# 4_cpu.net
KiCad netlist of a schematic drawn in Altium Designer
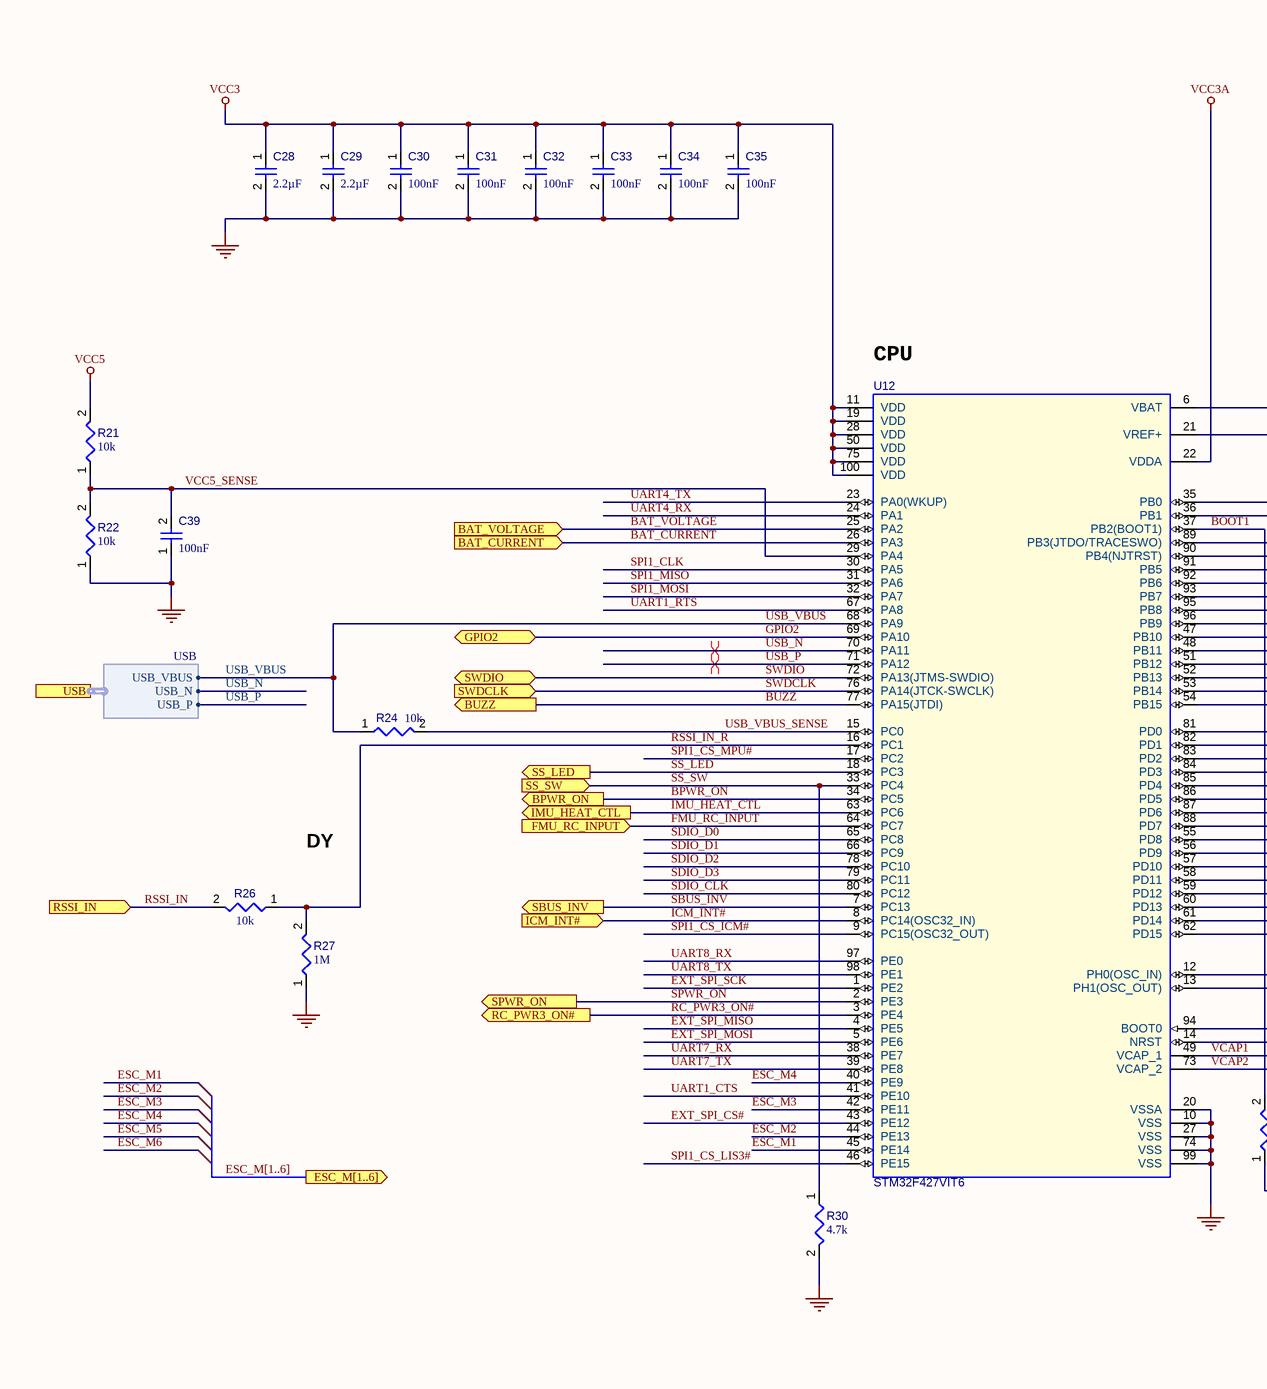
[diagram p0:  4_cpu.SchDoc, left]
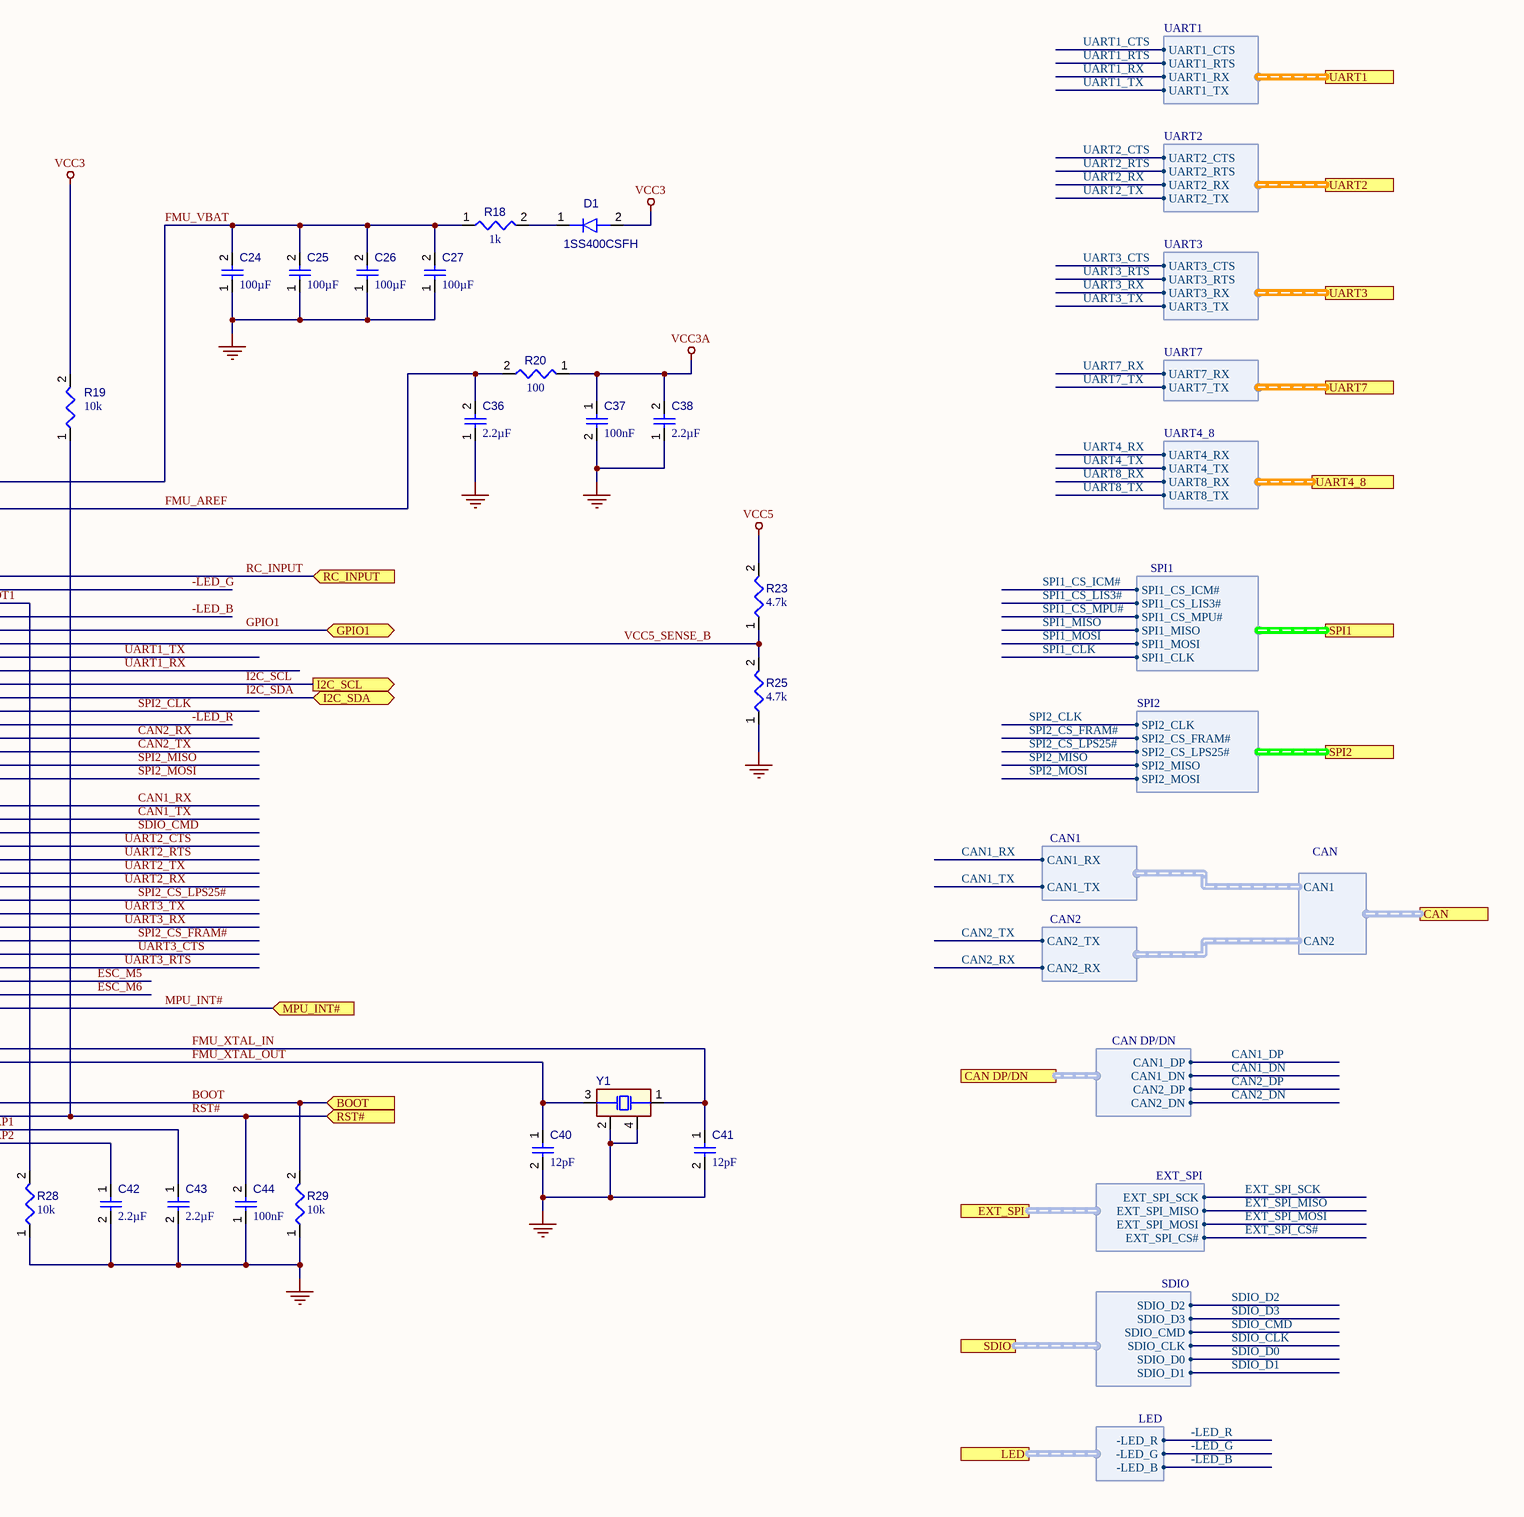
[diagram p1:  4_cpu.SchDoc, right]

(export (version "E")
  (design (tool "Eeschema 10.0.6"))
  (components
    (comp (ref "C24")
      (value "100µF")
      (footprint "CAPC0805(2012)145_L")
      (description "Chip Capacitor, 100µF +/-20%, 6.3V, 0805, Thickness 1.45 mm")
      (fields (field (name "TOLERANCE") "10%") (field (name "Comment") "Capacitor 100µF +/-20% 6.3V 0805"))
      (libsource (lib "MHH -  Altium Advanced Course A365 01") (part "CAP-NP-2"))
    )
    (comp (ref "C25")
      (value "100µF")
      (footprint "CAPC0805(2012)145_L")
      (description "Chip Capacitor, 100µF +/-20%, 6.3V, 0805, Thickness 1.45 mm")
      (fields (field (name "TOLERANCE") "10%") (field (name "Comment") "Capacitor 100µF +/-20% 6.3V 0805"))
      (libsource (lib "MHH -  Altium Advanced Course A365 01") (part "CAP-NP-2"))
    )
    (comp (ref "C26")
      (value "100µF")
      (footprint "CAPC0805(2012)145_L")
      (description "Chip Capacitor, 100µF +/-20%, 6.3V, 0805, Thickness 1.45 mm")
      (fields (field (name "TOLERANCE") "10%") (field (name "Comment") "Capacitor 100µF +/-20% 6.3V 0805"))
      (libsource (lib "MHH -  Altium Advanced Course A365 01") (part "CAP-NP-2"))
    )
    (comp (ref "C27")
      (value "100µF")
      (footprint "CAPC0805(2012)145_L")
      (description "Chip Capacitor, 100µF +/-20%, 6.3V, 0805, Thickness 1.45 mm")
      (fields (field (name "TOLERANCE") "10%") (field (name "Comment") "Capacitor 100µF +/-20% 6.3V 0805"))
      (libsource (lib "MHH -  Altium Advanced Course A365 01") (part "CAP-NP-2"))
    )
    (comp (ref "C28")
      (value "2.2µF")
      (footprint "CAPC0402(1005)60_L")
      (description "Chip Capacitor, 2,2µF +/-20%, 10V, 0402, Thickness 0.6 mm")
      (fields (field (name "TOLERANCE") "10%") (field (name "Comment") "Capacitor 2,2µF +/-20% 10V 0402"))
      (libsource (lib "MHH -  Altium Advanced Course A365 01") (part "CAP-NP-2"))
    )
    (comp (ref "C29")
      (value "2.2µF")
      (footprint "CAPC0402(1005)60_L")
      (description "Chip Capacitor, 2,2µF +/-20%, 10V, 0402, Thickness 0.6 mm")
      (fields (field (name "TOLERANCE") "10%") (field (name "Comment") "Capacitor 2,2µF +/-20% 10V 0402"))
      (libsource (lib "MHH -  Altium Advanced Course A365 01") (part "CAP-NP-2"))
    )
    (comp (ref "C30")
      (value "100nF")
      (footprint "CAPC0402(1005)60_L")
      (description "Chip Capacitor, 100nF +/-20%, 10V, 0402, Thickness 0.6 mm")
      (fields (field (name "TOLERANCE") "20%") (field (name "Comment") "Capacitor 100nF +/-20% 10V 0402"))
      (libsource (lib "MHH -  Altium Advanced Course A365 01") (part "CAP-NP-2"))
    )
    (comp (ref "C31")
      (value "100nF")
      (footprint "CAPC0402(1005)60_L")
      (description "Chip Capacitor, 100nF +/-20%, 10V, 0402, Thickness 0.6 mm")
      (fields (field (name "TOLERANCE") "20%") (field (name "Comment") "Capacitor 100nF +/-20% 10V 0402"))
      (libsource (lib "MHH -  Altium Advanced Course A365 01") (part "CAP-NP-2"))
    )
    (comp (ref "C32")
      (value "100nF")
      (footprint "CAPC0402(1005)60_L")
      (description "Chip Capacitor, 100nF +/-20%, 10V, 0402, Thickness 0.6 mm")
      (fields (field (name "TOLERANCE") "20%") (field (name "Comment") "Capacitor 100nF +/-20% 10V 0402"))
      (libsource (lib "MHH -  Altium Advanced Course A365 01") (part "CAP-NP-2"))
    )
    (comp (ref "C33")
      (value "100nF")
      (footprint "CAPC0402(1005)60_L")
      (description "Chip Capacitor, 100nF +/-20%, 10V, 0402, Thickness 0.6 mm")
      (fields (field (name "TOLERANCE") "20%") (field (name "Comment") "Capacitor 100nF +/-20% 10V 0402"))
      (libsource (lib "MHH -  Altium Advanced Course A365 01") (part "CAP-NP-2"))
    )
    (comp (ref "C34")
      (value "100nF")
      (footprint "CAPC0402(1005)60_L")
      (description "Chip Capacitor, 100nF +/-20%, 10V, 0402, Thickness 0.6 mm")
      (fields (field (name "TOLERANCE") "20%") (field (name "Comment") "Capacitor 100nF +/-20% 10V 0402"))
      (libsource (lib "MHH -  Altium Advanced Course A365 01") (part "CAP-NP-2"))
    )
    (comp (ref "C35")
      (value "100nF")
      (footprint "CAPC0402(1005)60_L")
      (description "Chip Capacitor, 100nF +/-20%, 10V, 0402, Thickness 0.6 mm")
      (fields (field (name "TOLERANCE") "20%") (field (name "Comment") "Capacitor 100nF +/-20% 10V 0402"))
      (libsource (lib "MHH -  Altium Advanced Course A365 01") (part "CAP-NP-2"))
    )
    (comp (ref "C36")
      (value "2.2µF")
      (footprint "CAPC0402(1005)60_L")
      (description "Chip Capacitor, 2,2µF +/-20%, 10V, 0402, Thickness 0.6 mm")
      (fields (field (name "TOLERANCE") "10%") (field (name "Comment") "Capacitor 2,2µF +/-20% 10V 0402"))
      (libsource (lib "MHH -  Altium Advanced Course A365 01") (part "CAP-NP-2"))
    )
    (comp (ref "C37")
      (value "100nF")
      (footprint "CAPC0402(1005)60_L")
      (description "Chip Capacitor, 100nF +/-20%, 10V, 0402, Thickness 0.6 mm")
      (fields (field (name "TOLERANCE") "20%") (field (name "Comment") "Capacitor 100nF +/-20% 10V 0402"))
      (libsource (lib "MHH -  Altium Advanced Course A365 01") (part "CAP-NP-2"))
    )
    (comp (ref "C38")
      (value "2.2µF")
      (footprint "CAPC0402(1005)60_L")
      (description "Chip Capacitor, 2,2µF +/-20%, 10V, 0402, Thickness 0.6 mm")
      (fields (field (name "TOLERANCE") "10%") (field (name "Comment") "Capacitor 2,2µF +/-20% 10V 0402"))
      (libsource (lib "MHH -  Altium Advanced Course A365 01") (part "CAP-NP-2"))
    )
    (comp (ref "C39")
      (value "100nF")
      (footprint "CAPC0402(1005)60_L")
      (description "Chip Capacitor, 100nF +/-20%, 10V, 0402, Thickness 0.6 mm")
      (fields (field (name "TOLERANCE") "20%") (field (name "Comment") "Capacitor 100nF +/-20% 10V 0402"))
      (libsource (lib "MHH -  Altium Advanced Course A365 01") (part "CAP-NP-2"))
    )
    (comp (ref "C40")
      (value "12pF")
      (footprint "CAPC0402(1005)33_L")
      (description "Chip Capacitor, 12pF +/-10%, 50V, 0402, Thickness 0.33 mm")
      (fields (field (name "TOLERANCE") "20%") (field (name "Comment") "Capacitor 12pF +/-10% 50V 0402"))
      (libsource (lib "MHH -  Altium Advanced Course A365 01") (part "CAP-NP-2"))
    )
    (comp (ref "C41")
      (value "12pF")
      (footprint "CAPC0402(1005)33_L")
      (description "Chip Capacitor, 12pF +/-10%, 50V, 0402, Thickness 0.33 mm")
      (fields (field (name "TOLERANCE") "20%") (field (name "Comment") "Capacitor 12pF +/-10% 50V 0402"))
      (libsource (lib "MHH -  Altium Advanced Course A365 01") (part "CAP-NP-2"))
    )
    (comp (ref "C42")
      (value "2.2µF")
      (footprint "CAPC0402(1005)60_L")
      (description "Chip Capacitor, 2,2µF +/-20%, 10V, 0402, Thickness 0.6 mm")
      (fields (field (name "TOLERANCE") "10%") (field (name "Comment") "Capacitor 2,2µF +/-20% 10V 0402"))
      (libsource (lib "MHH -  Altium Advanced Course A365 01") (part "CAP-NP-2"))
    )
    (comp (ref "C43")
      (value "2.2µF")
      (footprint "CAPC0402(1005)60_L")
      (description "Chip Capacitor, 2,2µF +/-20%, 10V, 0402, Thickness 0.6 mm")
      (fields (field (name "TOLERANCE") "10%") (field (name "Comment") "Capacitor 2,2µF +/-20% 10V 0402"))
      (libsource (lib "MHH -  Altium Advanced Course A365 01") (part "CAP-NP-2"))
    )
    (comp (ref "C44")
      (value "100nF")
      (footprint "CAPC0402(1005)60_L")
      (description "Chip Capacitor, 100nF +/-20%, 10V, 0402, Thickness 0.6 mm")
      (fields (field (name "TOLERANCE") "20%") (field (name "Comment") "Capacitor 100nF +/-20% 10V 0402"))
      (libsource (lib "MHH -  Altium Advanced Course A365 01") (part "CAP-NP-2"))
    )
    (comp (ref "D1")
      (value "1SS400CSFH")
      (footprint "ROHM-VMN2-2_V")
      (description "Switching Diode (High Speed Switching), 80 V, 100 mA, 2-Pin SOD-923, RoHS, Tape and Reel")
      (libsource (lib "MHH -  Altium Advanced Course A365 01") (part "D-KA-2"))
    )
    (comp (ref "R18")
      (value "1k")
      (footprint "RESC0402(1005)_L")
      (description "Chip Resistor, 1 kOhms, +/-5 %, 63 mW, -55 to 155 degC, 0402")
      (fields (field (name "TOLERANCE") "5%") (field (name "POWER") "63mW"))
      (libsource (lib "MHH -  Altium Advanced Course A365 01") (part "RES-2"))
    )
    (comp (ref "R19")
      (value "10k")
      (footprint "RESC0402(1005)_L")
      (description "Chip Resistor, 10 kOhms, +/-1 %, 63 mW, -55 to 125 degC, 0402")
      (fields (field (name "TOLERANCE") "1%") (field (name "POWER") "63mW"))
      (libsource (lib "MHH -  Altium Advanced Course A365 01") (part "RES-2"))
    )
    (comp (ref "R20")
      (value "100")
      (footprint "RESC0402(1005)_L")
      (description "Chip Resistor, 100 Ohms, +/-1 %, 63 mW, -55 to 155 degC, 0402")
      (fields (field (name "TOLERANCE") "1%") (field (name "POWER") "63mW"))
      (libsource (lib "MHH -  Altium Advanced Course A365 01") (part "RES-2"))
    )
    (comp (ref "R21")
      (value "10k")
      (footprint "RESC0402(1005)_L")
      (description "Chip Resistor, 10 kOhms, +/-1 %, 63 mW, -55 to 125 degC, 0402")
      (fields (field (name "TOLERANCE") "1%") (field (name "POWER") "63mW"))
      (libsource (lib "MHH -  Altium Advanced Course A365 01") (part "RES-2"))
    )
    (comp (ref "R22")
      (value "10k")
      (footprint "RESC0402(1005)_L")
      (description "Chip Resistor, 10 kOhms, +/-1 %, 63 mW, -55 to 125 degC, 0402")
      (fields (field (name "TOLERANCE") "1%") (field (name "POWER") "63mW"))
      (libsource (lib "MHH -  Altium Advanced Course A365 01") (part "RES-2"))
    )
    (comp (ref "R23")
      (value "4.7k")
      (footprint "RESC0402(1005)_L")
      (description "Chip Resistor, 4,7 kOhms, +/-1 %, 63 mW, -55 to 155 degC, 0402")
      (fields (field (name "TOLERANCE") "1%") (field (name "POWER") "63mW"))
      (libsource (lib "MHH -  Altium Advanced Course A365 01") (part "RES-2"))
    )
    (comp (ref "R24")
      (value "10k")
      (footprint "RESC0402(1005)_L")
      (description "Chip Resistor, 10 kOhms, +/-1 %, 63 mW, -55 to 125 degC, 0402")
      (fields (field (name "TOLERANCE") "1%") (field (name "POWER") "63mW"))
      (libsource (lib "MHH -  Altium Advanced Course A365 01") (part "RES-2"))
    )
    (comp (ref "R25")
      (value "4.7k")
      (footprint "RESC0402(1005)_L")
      (description "Chip Resistor, 4,7 kOhms, +/-1 %, 63 mW, -55 to 155 degC, 0402")
      (fields (field (name "TOLERANCE") "1%") (field (name "POWER") "63mW"))
      (libsource (lib "MHH -  Altium Advanced Course A365 01") (part "RES-2"))
    )
    (comp (ref "R26")
      (value "10k")
      (footprint "RESC0402(1005)_L")
      (description "Chip Resistor, 10 kOhms, +/-1 %, 63 mW, -55 to 125 degC, 0402")
      (fields (field (name "TOLERANCE") "1%") (field (name "POWER") "63mW"))
      (libsource (lib "MHH -  Altium Advanced Course A365 01") (part "RES-2"))
    )
    (comp (ref "R27")
      (value "1M")
      (footprint "RESC0402(1005)_L")
      (description "Chip Resistor, 1 MOhms, +/-5 %, 63 mW, -55 to 155 degC, 0402")
      (fields (field (name "TOLERANCE") "5%") (field (name "POWER") "63mW"))
      (libsource (lib "MHH -  Altium Advanced Course A365 01") (part "RES-2"))
    )
    (comp (ref "R28")
      (value "10k")
      (footprint "RESC0402(1005)_L")
      (description "Chip Resistor, 10 kOhms, +/-1 %, 63 mW, -55 to 125 degC, 0402")
      (fields (field (name "TOLERANCE") "1%") (field (name "POWER") "63mW"))
      (libsource (lib "MHH -  Altium Advanced Course A365 01") (part "RES-2"))
    )
    (comp (ref "R29")
      (value "10k")
      (footprint "RESC0402(1005)_L")
      (description "Chip Resistor, 10 kOhms, +/-1 %, 63 mW, -55 to 125 degC, 0402")
      (fields (field (name "TOLERANCE") "1%") (field (name "POWER") "63mW"))
      (libsource (lib "MHH -  Altium Advanced Course A365 01") (part "RES-2"))
    )
    (comp (ref "R30")
      (value "4.7k")
      (footprint "RESC0402(1005)_L")
      (description "Chip Resistor, 4,7 kOhms, +/-1 %, 63 mW, -55 to 155 degC, 0402")
      (fields (field (name "TOLERANCE") "1%") (field (name "POWER") "63mW"))
      (libsource (lib "MHH -  Altium Advanced Course A365 01") (part "RES-2"))
    )
    (comp (ref "U12")
      (value "STM32F427VIT6")
      (footprint "STM-LQFP100")
      (libsource (lib "MHH -  Altium Advanced Course A365 01") (part "CMP-00125-5"))
    )
    (comp (ref "Y1")
      (value "FA-12824.0000MF10Z-W3")
      (footprint "EPSON-FA-128_V")
      (description "Crystal, 24 MHz, +/- 10 ppm, -20 to 75 degC, 4-Pin SMD, RoHS, Tape and Reel")
      (libsource (lib "MHH -  Altium Advanced Course A365 01") (part "CMP-00014-7"))
    )
  )
  (nets
    (net (code "16") (name "/-LED_B") (class "Default")
      (node (ref "U12") (pin "89") (pinfunction "PB3(JTDO/TRACESWO)_89") (pintype "bidirectional"))
    )
    (net (code "17") (name "/-LED_G") (class "Default")
      (node (ref "U12") (pin "36") (pinfunction "PB1_36") (pintype "bidirectional"))
    )
    (net (code "18") (name "/-LED_R") (class "Default")
      (node (ref "U12") (pin "48") (pinfunction "PB11_48") (pintype "bidirectional"))
    )
    (net (code "19") (name "/BAT_CURRENT") (class "Default")
      (node (ref "U12") (pin "26") (pinfunction "PA3_26") (pintype "bidirectional"))
    )
    (net (code "20") (name "/BAT_VOLTAGE") (class "Default")
      (node (ref "U12") (pin "25") (pinfunction "PA2_25") (pintype "bidirectional"))
    )
    (net (code "21") (name "/BOOT") (class "Default")
      (node (ref "R29") (pin "2") (pinfunction "2_2") (pintype "passive"))
      (node (ref "U12") (pin "94") (pinfunction "BOOT0_94") (pintype "input"))
    )
    (net (code "22") (name "/BOOT1") (class "Default")
      (node (ref "R28") (pin "2") (pinfunction "2_2") (pintype "passive"))
      (node (ref "U12") (pin "37") (pinfunction "PB2(BOOT1)_37") (pintype "bidirectional"))
    )
    (net (code "23") (name "/BPWR_ON") (class "Default")
      (node (ref "U12") (pin "34") (pinfunction "PC5_34") (pintype "bidirectional"))
    )
    (net (code "24") (name "/BUZZ") (class "Default")
      (node (ref "U12") (pin "77") (pinfunction "PA15(JTDI)_77") (pintype "bidirectional"))
    )
    (net (code "27") (name "/CAN1_RX") (class "Default")
      (node (ref "U12") (pin "81") (pinfunction "PD0_81") (pintype "bidirectional"))
    )
    (net (code "28") (name "/CAN1_TX") (class "Default")
      (node (ref "U12") (pin "82") (pinfunction "PD1_82") (pintype "bidirectional"))
    )
    (net (code "31") (name "/CAN2_RX") (class "Default")
      (node (ref "U12") (pin "51") (pinfunction "PB12_51") (pintype "bidirectional"))
    )
    (net (code "32") (name "/CAN2_TX") (class "Default")
      (node (ref "U12") (pin "52") (pinfunction "PB13_52") (pintype "bidirectional"))
    )
    (net (code "34") (name "/ESC_M1") (class "Default")
      (node (ref "U12") (pin "45") (pinfunction "PE14_45") (pintype "bidirectional"))
    )
    (net (code "35") (name "/ESC_M2") (class "Default")
      (node (ref "U12") (pin "44") (pinfunction "PE13_44") (pintype "bidirectional"))
    )
    (net (code "36") (name "/ESC_M3") (class "Default")
      (node (ref "U12") (pin "42") (pinfunction "PE11_42") (pintype "bidirectional"))
    )
    (net (code "37") (name "/ESC_M4") (class "Default")
      (node (ref "U12") (pin "40") (pinfunction "PE9_40") (pintype "bidirectional"))
    )
    (net (code "38") (name "/ESC_M5") (class "Default")
      (node (ref "U12") (pin "60") (pinfunction "PD13_60") (pintype "bidirectional"))
    )
    (net (code "39") (name "/ESC_M6") (class "Default")
      (node (ref "U12") (pin "61") (pinfunction "PD14_61") (pintype "bidirectional"))
    )
    (net (code "41") (name "/EXT_SPI_CS#") (class "Default")
      (node (ref "U12") (pin "43") (pinfunction "PE12_43") (pintype "bidirectional"))
    )
    (net (code "42") (name "/EXT_SPI_MISO") (class "Default")
      (node (ref "U12") (pin "4") (pinfunction "PE5_4") (pintype "bidirectional"))
    )
    (net (code "43") (name "/EXT_SPI_MOSI") (class "Default")
      (node (ref "U12") (pin "5") (pinfunction "PE6_5") (pintype "bidirectional"))
    )
    (net (code "44") (name "/EXT_SPI_SCK") (class "Default")
      (node (ref "U12") (pin "1") (pinfunction "PE2_1") (pintype "bidirectional"))
    )
    (net (code "45") (name "/FMU_AREF") (class "Default")
      (node (ref "C36") (pin "2") (pinfunction "2_2") (pintype "passive"))
      (node (ref "R20") (pin "2") (pinfunction "2_2") (pintype "passive"))
      (node (ref "U12") (pin "21") (pinfunction "VREF+_21") (pintype "power_in"))
    )
    (net (code "46") (name "/FMU_RC_INPUT") (class "Default")
      (node (ref "U12") (pin "64") (pinfunction "PC7_64") (pintype "bidirectional"))
    )
    (net (code "47") (name "/FMU_VBAT") (class "Default")
      (node (ref "C24") (pin "2") (pinfunction "2_2") (pintype "passive"))
      (node (ref "C25") (pin "2") (pinfunction "2_2") (pintype "passive"))
      (node (ref "C26") (pin "2") (pinfunction "2_2") (pintype "passive"))
      (node (ref "C27") (pin "2") (pinfunction "2_2") (pintype "passive"))
      (node (ref "R18") (pin "1") (pinfunction "1_1") (pintype "passive"))
      (node (ref "U12") (pin "6") (pinfunction "VBAT_6") (pintype "power_in"))
    )
    (net (code "48") (name "/FMU_XTAL_IN") (class "Default")
      (node (ref "C41") (pin "1") (pinfunction "1_1") (pintype "passive"))
      (node (ref "U12") (pin "12") (pinfunction "PH0(OSC_IN)_12") (pintype "bidirectional"))
      (node (ref "Y1") (pin "1") (pinfunction "X1_1") (pintype "passive"))
    )
    (net (code "49") (name "/FMU_XTAL_OUT") (class "Default")
      (node (ref "C40") (pin "1") (pinfunction "1_1") (pintype "passive"))
      (node (ref "U12") (pin "13") (pinfunction "PH1(OSC_OUT)_13") (pintype "bidirectional"))
      (node (ref "Y1") (pin "3") (pinfunction "X2_3") (pintype "passive"))
    )
    (net (code "50") (name "/GPIO1") (class "Default")
      (node (ref "U12") (pin "90") (pinfunction "PB4(NJTRST)_90") (pintype "bidirectional"))
    )
    (net (code "51") (name "/GPIO2") (class "Default")
      (node (ref "U12") (pin "69") (pinfunction "PA10_69") (pintype "bidirectional"))
    )
    (net (code "52") (name "/I2C_SCL") (class "Default")
      (node (ref "U12") (pin "95") (pinfunction "PB8_95") (pintype "bidirectional"))
    )
    (net (code "53") (name "/I2C_SDA") (class "Default")
      (node (ref "U12") (pin "96") (pinfunction "PB9_96") (pintype "bidirectional"))
    )
    (net (code "54") (name "/ICM_INT#") (class "Default")
      (node (ref "U12") (pin "8") (pinfunction "PC14(OSC32_IN)_8") (pintype "bidirectional"))
    )
    (net (code "55") (name "/IMU_HEAT_CTL") (class "Default")
      (node (ref "U12") (pin "63") (pinfunction "PC6_63") (pintype "bidirectional"))
    )
    (net (code "56") (name "/MPU_INT#") (class "Default")
      (node (ref "U12") (pin "62") (pinfunction "PD15_62") (pintype "bidirectional"))
    )
    (net (code "57") (name "/RC_INPUT") (class "Default")
      (node (ref "U12") (pin "35") (pinfunction "PB0_35") (pintype "bidirectional"))
    )
    (net (code "58") (name "/RC_PWR3_ON#") (class "Default")
      (node (ref "U12") (pin "3") (pinfunction "PE4_3") (pintype "bidirectional"))
    )
    (net (code "59") (name "/RSSI_IN") (class "Default")
      (node (ref "R26") (pin "2") (pinfunction "2_2") (pintype "passive"))
    )
    (net (code "60") (name "/RSSI_IN_R") (class "Default")
      (node (ref "R26") (pin "1") (pinfunction "1_1") (pintype "passive"))
      (node (ref "R27") (pin "2") (pinfunction "2_2") (pintype "passive"))
      (node (ref "U12") (pin "16") (pinfunction "PC1_16") (pintype "bidirectional"))
    )
    (net (code "61") (name "/RST#") (class "Default")
      (node (ref "C44") (pin "2") (pinfunction "2_2") (pintype "passive"))
      (node (ref "R19") (pin "1") (pinfunction "1_1") (pintype "passive"))
      (node (ref "U12") (pin "14") (pinfunction "NRST_14") (pintype "bidirectional"))
    )
    (net (code "62") (name "/SBUS_INV") (class "Default")
      (node (ref "U12") (pin "7") (pinfunction "PC13_7") (pintype "bidirectional"))
    )
    (net (code "63") (name "/SDIO_CLK") (class "Default")
      (node (ref "U12") (pin "80") (pinfunction "PC12_80") (pintype "bidirectional"))
    )
    (net (code "64") (name "/SDIO_CMD") (class "Default")
      (node (ref "U12") (pin "83") (pinfunction "PD2_83") (pintype "bidirectional"))
    )
    (net (code "65") (name "/SDIO_D0") (class "Default")
      (node (ref "U12") (pin "65") (pinfunction "PC8_65") (pintype "bidirectional"))
    )
    (net (code "66") (name "/SDIO_D1") (class "Default")
      (node (ref "U12") (pin "66") (pinfunction "PC9_66") (pintype "bidirectional"))
    )
    (net (code "67") (name "/SDIO_D2") (class "Default")
      (node (ref "U12") (pin "78") (pinfunction "PC10_78") (pintype "bidirectional"))
    )
    (net (code "68") (name "/SDIO_D3") (class "Default")
      (node (ref "U12") (pin "79") (pinfunction "PC11_79") (pintype "bidirectional"))
    )
    (net (code "69") (name "/SPI1_CLK") (class "Default")
      (node (ref "U12") (pin "30") (pinfunction "PA5_30") (pintype "bidirectional"))
    )
    (net (code "70") (name "/SPI1_CS_ICM#") (class "Default")
      (node (ref "U12") (pin "9") (pinfunction "PC15(OSC32_OUT)_9") (pintype "bidirectional"))
    )
    (net (code "71") (name "/SPI1_CS_LIS3#") (class "Default")
      (node (ref "U12") (pin "46") (pinfunction "PE15_46") (pintype "bidirectional"))
    )
    (net (code "72") (name "/SPI1_CS_MPU#") (class "Default")
      (node (ref "U12") (pin "17") (pinfunction "PC2_17") (pintype "bidirectional"))
    )
    (net (code "73") (name "/SPI1_MISO") (class "Default")
      (node (ref "U12") (pin "31") (pinfunction "PA6_31") (pintype "bidirectional"))
    )
    (net (code "74") (name "/SPI1_MOSI") (class "Default")
      (node (ref "U12") (pin "32") (pinfunction "PA7_32") (pintype "bidirectional"))
    )
    (net (code "75") (name "/SPI2_CLK") (class "Default")
      (node (ref "U12") (pin "47") (pinfunction "PB10_47") (pintype "bidirectional"))
    )
    (net (code "76") (name "/SPI2_CS_FRAM#") (class "Default")
      (node (ref "U12") (pin "57") (pinfunction "PD10_57") (pintype "bidirectional"))
    )
    (net (code "77") (name "/SPI2_CS_LPS25#") (class "Default")
      (node (ref "U12") (pin "88") (pinfunction "PD7_88") (pintype "bidirectional"))
    )
    (net (code "78") (name "/SPI2_MISO") (class "Default")
      (node (ref "U12") (pin "53") (pinfunction "PB14_53") (pintype "bidirectional"))
    )
    (net (code "79") (name "/SPI2_MOSI") (class "Default")
      (node (ref "U12") (pin "54") (pinfunction "PB15_54") (pintype "bidirectional"))
    )
    (net (code "80") (name "/SPWR_ON") (class "Default")
      (node (ref "U12") (pin "2") (pinfunction "PE3_2") (pintype "bidirectional"))
    )
    (net (code "81") (name "/SS_LED") (class "Default")
      (node (ref "U12") (pin "18") (pinfunction "PC3_18") (pintype "bidirectional"))
    )
    (net (code "82") (name "/SS_SW") (class "Default")
      (node (ref "R30") (pin "1") (pinfunction "1_1") (pintype "passive"))
      (node (ref "U12") (pin "33") (pinfunction "PC4_33") (pintype "bidirectional"))
    )
    (net (code "83") (name "/SWDCLK") (class "Default")
      (node (ref "U12") (pin "76") (pinfunction "PA14(JTCK-SWCLK)_76") (pintype "bidirectional"))
    )
    (net (code "84") (name "/SWDIO") (class "Default")
      (node (ref "U12") (pin "72") (pinfunction "PA13(JTMS-SWDIO)_72") (pintype "bidirectional"))
    )
    (net (code "85") (name "/UART1_CTS") (class "Default")
      (node (ref "U12") (pin "41") (pinfunction "PE10_41") (pintype "bidirectional"))
    )
    (net (code "86") (name "/UART1_RTS") (class "Default")
      (node (ref "U12") (pin "67") (pinfunction "PA8_67") (pintype "bidirectional"))
    )
    (net (code "87") (name "/UART1_RX") (class "Default")
      (node (ref "U12") (pin "93") (pinfunction "PB7_93") (pintype "bidirectional"))
    )
    (net (code "88") (name "/UART1_TX") (class "Default")
      (node (ref "U12") (pin "92") (pinfunction "PB6_92") (pintype "bidirectional"))
    )
    (net (code "89") (name "/UART2_CTS") (class "Default")
      (node (ref "U12") (pin "84") (pinfunction "PD3_84") (pintype "bidirectional"))
    )
    (net (code "90") (name "/UART2_RTS") (class "Default")
      (node (ref "U12") (pin "85") (pinfunction "PD4_85") (pintype "bidirectional"))
    )
    (net (code "91") (name "/UART2_RX") (class "Default")
      (node (ref "U12") (pin "87") (pinfunction "PD6_87") (pintype "bidirectional"))
    )
    (net (code "92") (name "/UART2_TX") (class "Default")
      (node (ref "U12") (pin "86") (pinfunction "PD5_86") (pintype "bidirectional"))
    )
    (net (code "93") (name "/UART3_CTS") (class "Default")
      (node (ref "U12") (pin "58") (pinfunction "PD11_58") (pintype "bidirectional"))
    )
    (net (code "94") (name "/UART3_RTS") (class "Default")
      (node (ref "U12") (pin "59") (pinfunction "PD12_59") (pintype "bidirectional"))
    )
    (net (code "95") (name "/UART3_RX") (class "Default")
      (node (ref "U12") (pin "56") (pinfunction "PD9_56") (pintype "bidirectional"))
    )
    (net (code "96") (name "/UART3_TX") (class "Default")
      (node (ref "U12") (pin "55") (pinfunction "PD8_55") (pintype "bidirectional"))
    )
    (net (code "97") (name "/UART4_RX") (class "Default")
      (node (ref "U12") (pin "24") (pinfunction "PA1_24") (pintype "bidirectional"))
    )
    (net (code "98") (name "/UART4_TX") (class "Default")
      (node (ref "U12") (pin "23") (pinfunction "PA0(WKUP)_23") (pintype "bidirectional"))
    )
    (net (code "99") (name "/UART7_RX") (class "Default")
      (node (ref "U12") (pin "38") (pinfunction "PE7_38") (pintype "bidirectional"))
    )
    (net (code "100") (name "/UART7_TX") (class "Default")
      (node (ref "U12") (pin "39") (pinfunction "PE8_39") (pintype "bidirectional"))
    )
    (net (code "101") (name "/UART8_RX") (class "Default")
      (node (ref "U12") (pin "97") (pinfunction "PE0_97") (pintype "bidirectional"))
    )
    (net (code "102") (name "/UART8_TX") (class "Default")
      (node (ref "U12") (pin "98") (pinfunction "PE1_98") (pintype "bidirectional"))
    )
    (net (code "103") (name "/USB_N") (class "Default")
      (node (ref "U12") (pin "70") (pinfunction "PA11_70") (pintype "bidirectional"))
    )
    (net (code "104") (name "/USB_P") (class "Default")
      (node (ref "U12") (pin "71") (pinfunction "PA12_71") (pintype "bidirectional"))
    )
    (net (code "105") (name "/USB_VBUS") (class "Default")
      (node (ref "R24") (pin "1") (pinfunction "1_1") (pintype "passive"))
      (node (ref "U12") (pin "68") (pinfunction "PA9_68") (pintype "bidirectional"))
    )
    (net (code "106") (name "/USB_VBUS_SENSE") (class "Default")
      (node (ref "R24") (pin "2") (pinfunction "2_2") (pintype "passive"))
      (node (ref "U12") (pin "15") (pinfunction "PC0_15") (pintype "bidirectional"))
    )
    (net (code "107") (name "/VCAP1") (class "Default")
      (node (ref "C43") (pin "1") (pinfunction "1_1") (pintype "passive"))
      (node (ref "U12") (pin "49") (pinfunction "VCAP_1_49") (pintype "passive"))
    )
    (net (code "108") (name "/VCAP2") (class "Default")
      (node (ref "C42") (pin "1") (pinfunction "1_1") (pintype "passive"))
      (node (ref "U12") (pin "73") (pinfunction "VCAP_2_73") (pintype "passive"))
    )
    (net (code "109") (name "/VCC5_SENSE") (class "Default")
      (node (ref "C39") (pin "2") (pinfunction "2_2") (pintype "passive"))
      (node (ref "R21") (pin "1") (pinfunction "1_1") (pintype "passive"))
      (node (ref "R22") (pin "2") (pinfunction "2_2") (pintype "passive"))
      (node (ref "U12") (pin "29") (pinfunction "PA4_29") (pintype "bidirectional"))
    )
    (net (code "110") (name "/VCC5_SENSE_B") (class "Default")
      (node (ref "R23") (pin "1") (pinfunction "1_1") (pintype "passive"))
      (node (ref "R25") (pin "2") (pinfunction "2_2") (pintype "passive"))
      (node (ref "U12") (pin "91") (pinfunction "PB5_91") (pintype "bidirectional"))
    )
    (net (code "125") (name "GND") (class "Default")
      (node (ref "C24") (pin "1") (pinfunction "1_1") (pintype "passive"))
      (node (ref "C25") (pin "1") (pinfunction "1_1") (pintype "passive"))
      (node (ref "C26") (pin "1") (pinfunction "1_1") (pintype "passive"))
      (node (ref "C27") (pin "1") (pinfunction "1_1") (pintype "passive"))
      (node (ref "C28") (pin "2") (pinfunction "2_2") (pintype "passive"))
      (node (ref "C29") (pin "2") (pinfunction "2_2") (pintype "passive"))
      (node (ref "C30") (pin "2") (pinfunction "2_2") (pintype "passive"))
      (node (ref "C31") (pin "2") (pinfunction "2_2") (pintype "passive"))
      (node (ref "C32") (pin "2") (pinfunction "2_2") (pintype "passive"))
      (node (ref "C33") (pin "2") (pinfunction "2_2") (pintype "passive"))
      (node (ref "C34") (pin "2") (pinfunction "2_2") (pintype "passive"))
      (node (ref "C35") (pin "2") (pinfunction "2_2") (pintype "passive"))
      (node (ref "C36") (pin "1") (pinfunction "1_1") (pintype "passive"))
      (node (ref "C37") (pin "2") (pinfunction "2_2") (pintype "passive"))
      (node (ref "C38") (pin "1") (pinfunction "1_1") (pintype "passive"))
      (node (ref "C39") (pin "1") (pinfunction "1_1") (pintype "passive"))
      (node (ref "C40") (pin "2") (pinfunction "2_2") (pintype "passive"))
      (node (ref "C41") (pin "2") (pinfunction "2_2") (pintype "passive"))
      (node (ref "C42") (pin "2") (pinfunction "2_2") (pintype "passive"))
      (node (ref "C43") (pin "2") (pinfunction "2_2") (pintype "passive"))
      (node (ref "C44") (pin "1") (pinfunction "1_1") (pintype "passive"))
      (node (ref "R22") (pin "1") (pinfunction "1_1") (pintype "passive"))
      (node (ref "R25") (pin "1") (pinfunction "1_1") (pintype "passive"))
      (node (ref "R27") (pin "1") (pinfunction "1_1") (pintype "passive"))
      (node (ref "R28") (pin "1") (pinfunction "1_1") (pintype "passive"))
      (node (ref "R29") (pin "1") (pinfunction "1_1") (pintype "passive"))
      (node (ref "R30") (pin "2") (pinfunction "2_2") (pintype "passive"))
      (node (ref "U12") (pin "10") (pinfunction "VSS_10") (pintype "power_in"))
      (node (ref "U12") (pin "20") (pinfunction "VSSA_20") (pintype "power_in"))
      (node (ref "U12") (pin "27") (pinfunction "VSS_27") (pintype "power_in"))
      (node (ref "U12") (pin "74") (pinfunction "VSS_74") (pintype "power_in"))
      (node (ref "U12") (pin "99") (pinfunction "VSS_99") (pintype "power_in"))
      (node (ref "Y1") (pin "2") (pinfunction "NC_2") (pintype "power_in"))
      (node (ref "Y1") (pin "4") (pinfunction "NC_4") (pintype "power_in"))
    )
    (net (code "126") (name "Net-(D1-K)") (class "Default")
      (node (ref "D1") (pin "1") (pinfunction "K_1") (pintype "passive"))
      (node (ref "R18") (pin "2") (pinfunction "2_2") (pintype "passive"))
    )
    (net (code "127") (name "VCC3") (class "Default")
      (node (ref "C28") (pin "1") (pinfunction "1_1") (pintype "passive"))
      (node (ref "C29") (pin "1") (pinfunction "1_1") (pintype "passive"))
      (node (ref "C30") (pin "1") (pinfunction "1_1") (pintype "passive"))
      (node (ref "C31") (pin "1") (pinfunction "1_1") (pintype "passive"))
      (node (ref "C32") (pin "1") (pinfunction "1_1") (pintype "passive"))
      (node (ref "C33") (pin "1") (pinfunction "1_1") (pintype "passive"))
      (node (ref "C34") (pin "1") (pinfunction "1_1") (pintype "passive"))
      (node (ref "C35") (pin "1") (pinfunction "1_1") (pintype "passive"))
      (node (ref "D1") (pin "2") (pinfunction "A_2") (pintype "passive"))
      (node (ref "R19") (pin "2") (pinfunction "2_2") (pintype "passive"))
      (node (ref "U12") (pin "100") (pinfunction "VDD_100") (pintype "power_in"))
      (node (ref "U12") (pin "11") (pinfunction "VDD_11") (pintype "power_in"))
      (node (ref "U12") (pin "19") (pinfunction "VDD_19") (pintype "power_in"))
      (node (ref "U12") (pin "28") (pinfunction "VDD_28") (pintype "power_in"))
      (node (ref "U12") (pin "50") (pinfunction "VDD_50") (pintype "power_in"))
      (node (ref "U12") (pin "75") (pinfunction "VDD_75") (pintype "power_in"))
    )
    (net (code "128") (name "VCC3A") (class "Default")
      (node (ref "C37") (pin "1") (pinfunction "1_1") (pintype "passive"))
      (node (ref "C38") (pin "2") (pinfunction "2_2") (pintype "passive"))
      (node (ref "R20") (pin "1") (pinfunction "1_1") (pintype "passive"))
      (node (ref "U12") (pin "22") (pinfunction "VDDA_22") (pintype "power_in"))
    )
    (net (code "129") (name "VCC5") (class "Default")
      (node (ref "R21") (pin "2") (pinfunction "2_2") (pintype "passive"))
      (node (ref "R23") (pin "2") (pinfunction "2_2") (pintype "passive"))
    )
  )
)
